# swbox_midi.net
KiCad netlist of a schematic drawn in EAGLE
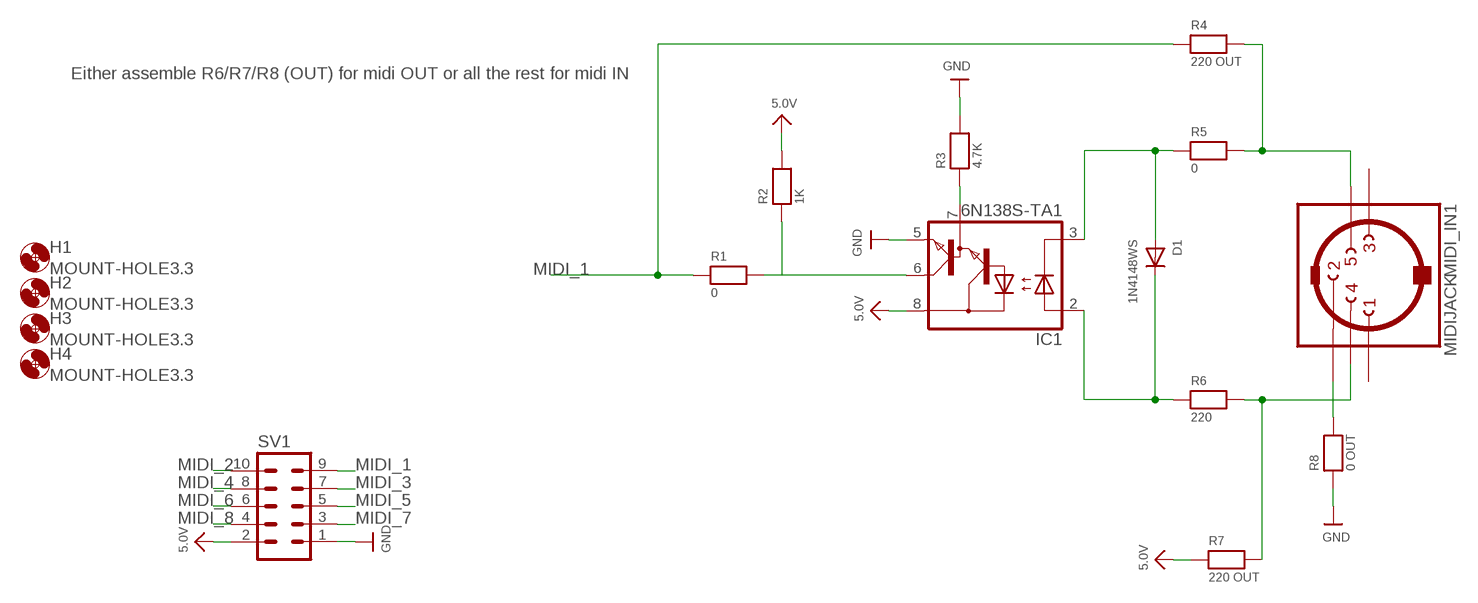
[diagram p0: schematic, sheet 1]
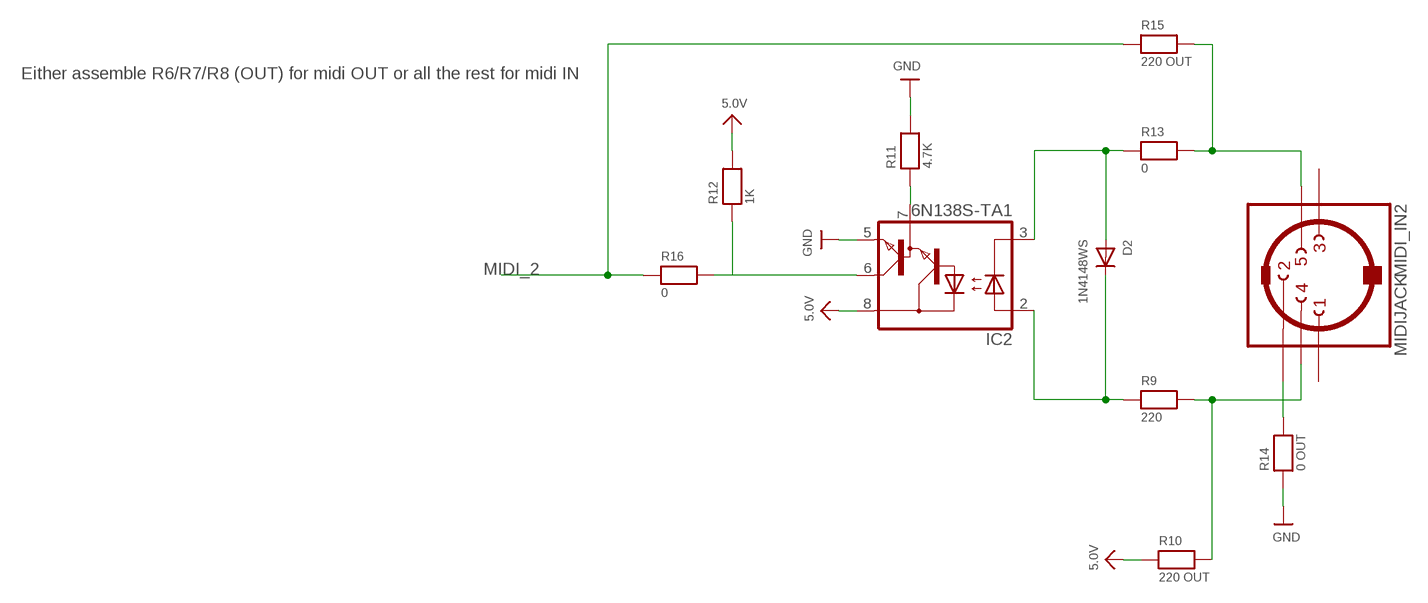
[diagram p1: schematic, sheet 2]
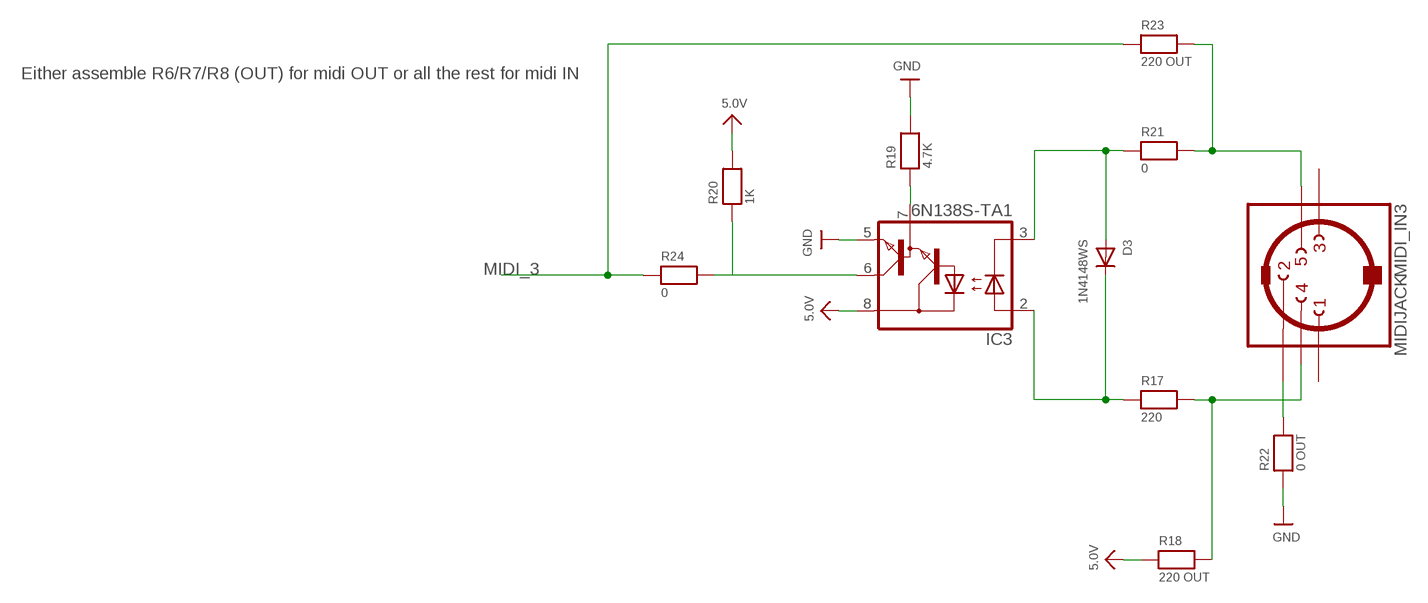
[diagram p2: schematic, sheet 3]
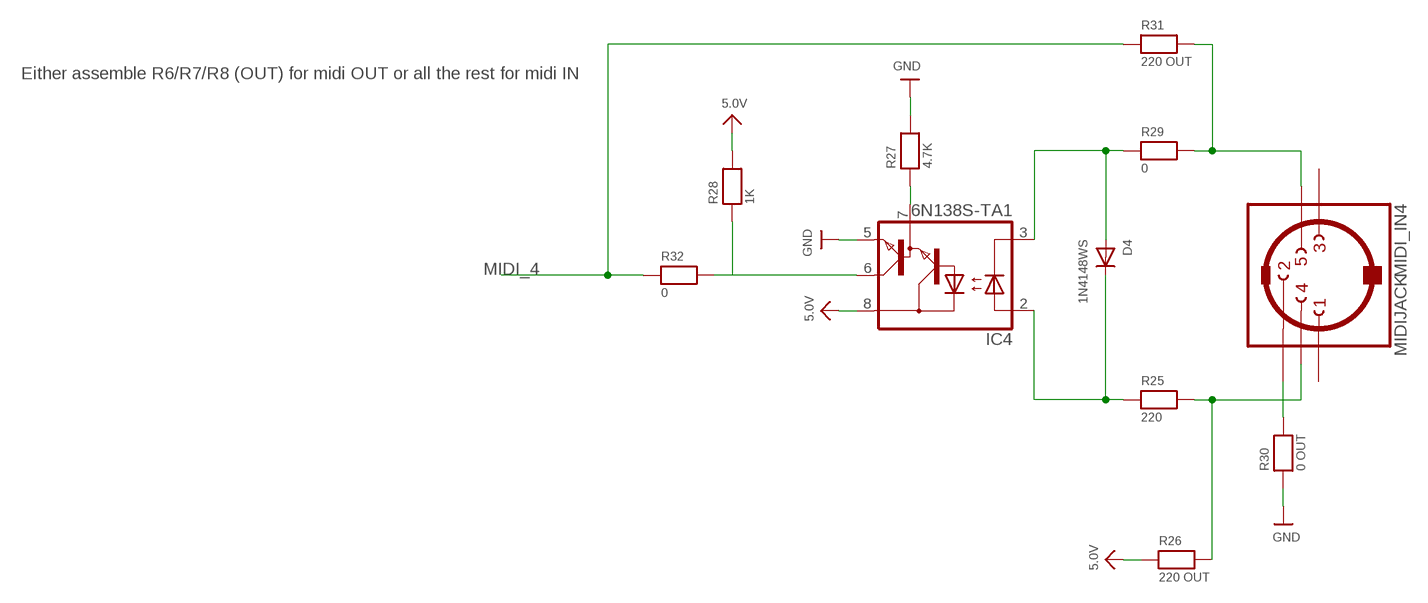
[diagram p3: schematic, sheet 4]
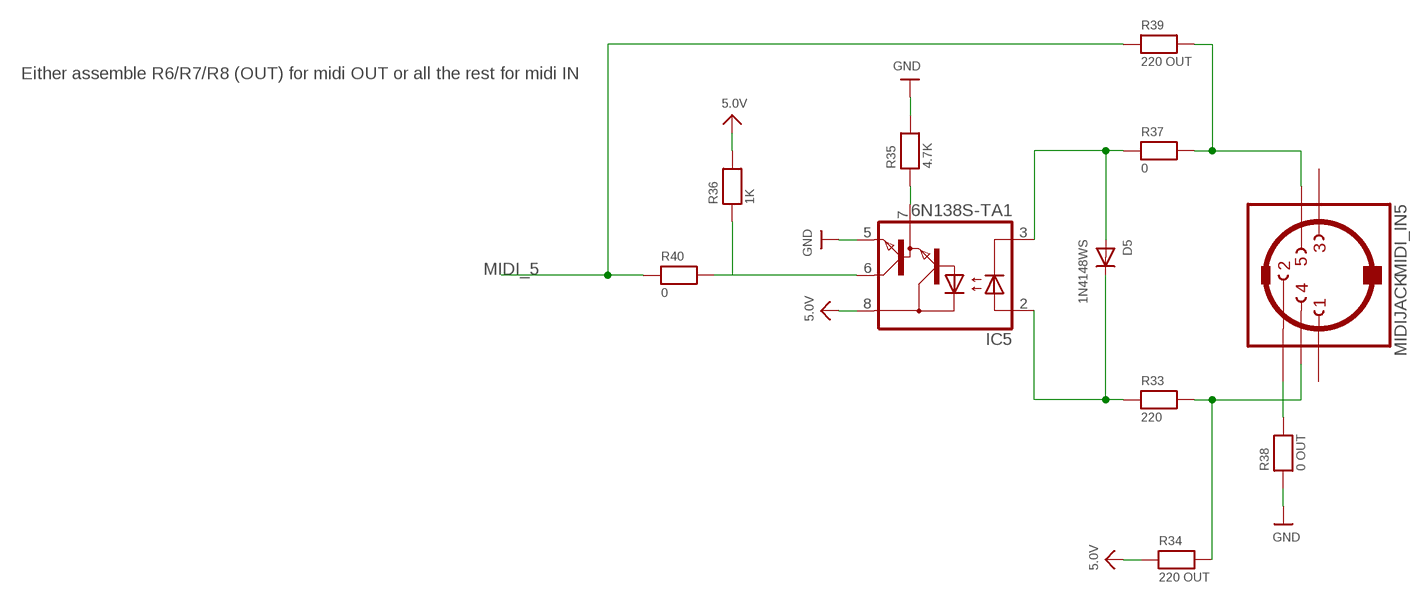
[diagram p4: schematic, sheet 5]
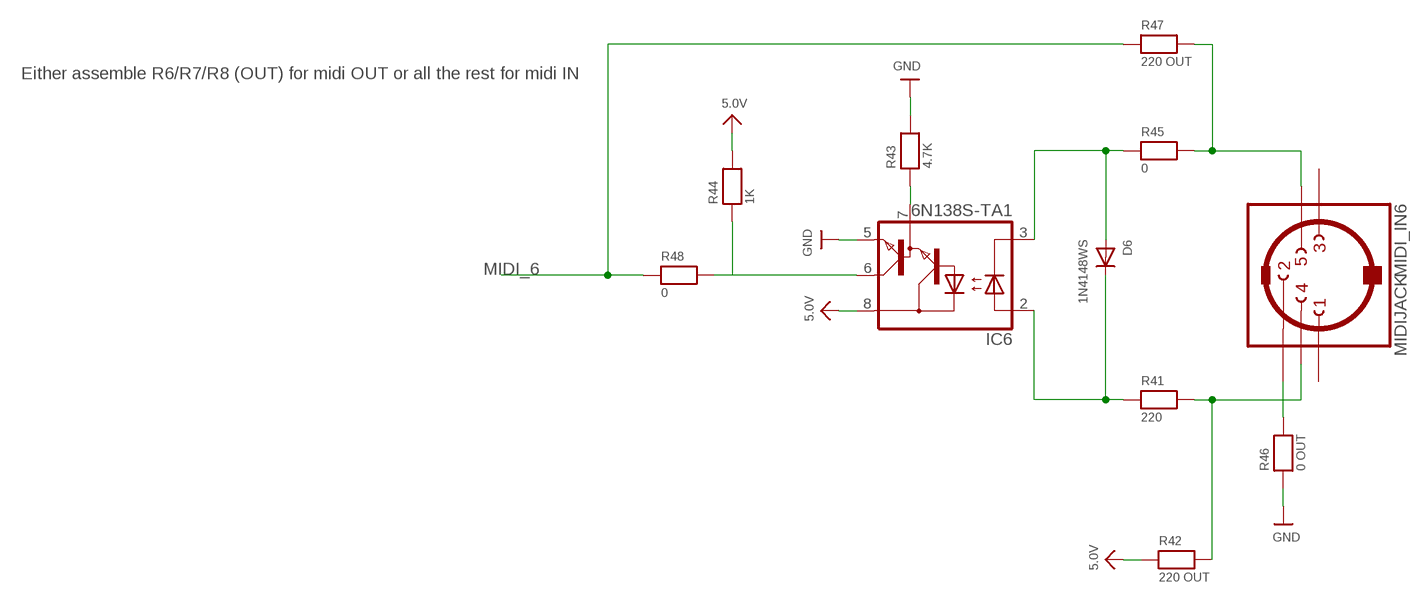
[diagram p5: schematic, sheet 6]
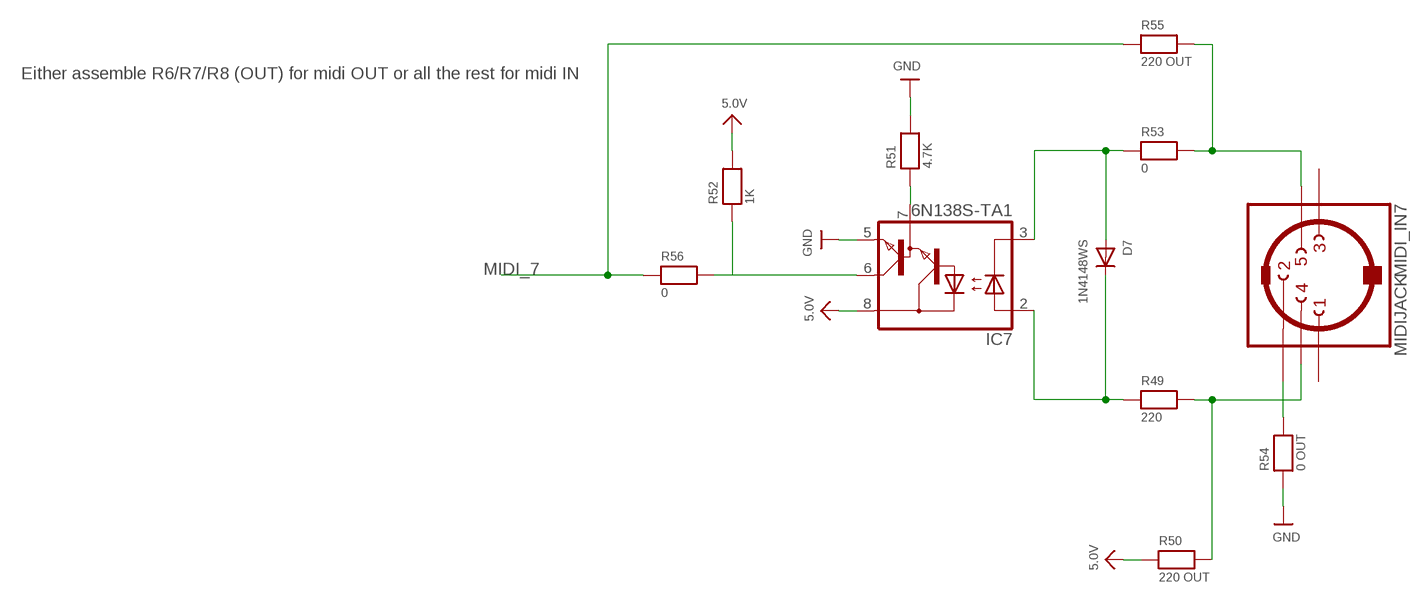
[diagram p6: schematic, sheet 7]
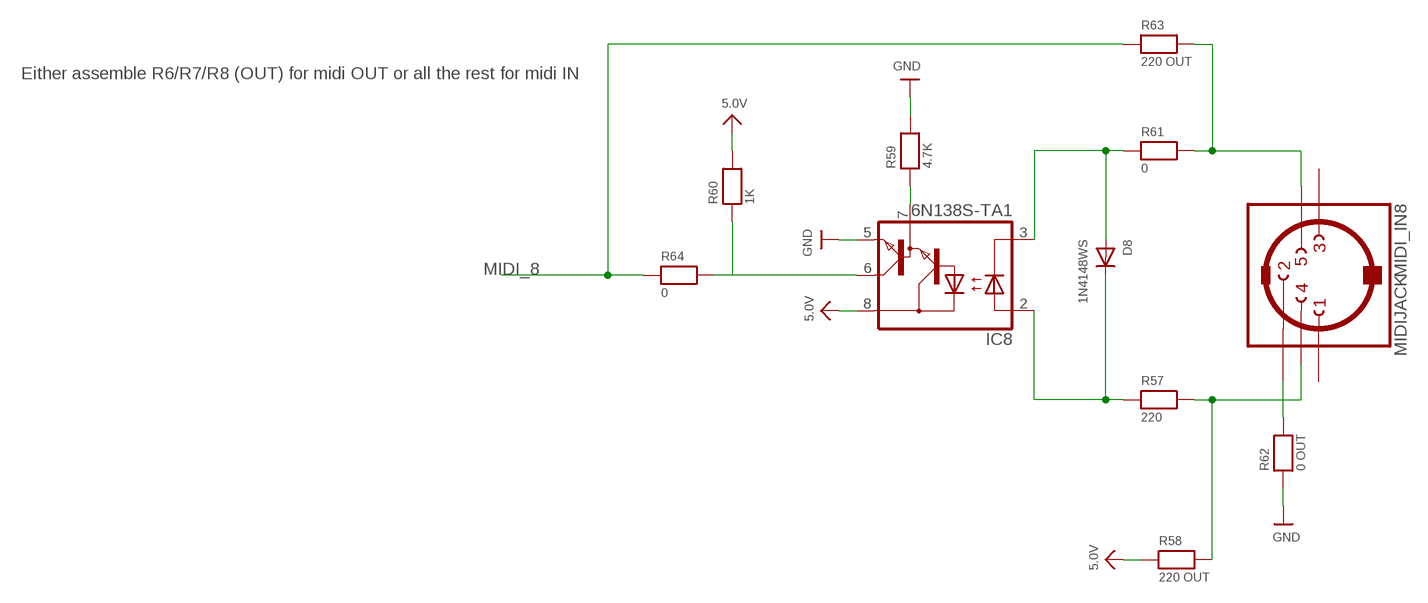
[diagram p7: schematic, sheet 8]

(export (version "E")
  (design (tool "Eeschema 10.0.6"))
  (components
    (comp (ref "D1")
      (value "1N4148WS")
      (footprint "eagle-import:SOD-323")
      (libsource (lib "eagle-import") (part "DIODESOD-323"))
    )
    (comp (ref "H1")
      (value "MOUNT-HOLE3.3")
      (footprint "eagle-import:3,3")
      (libsource (lib "eagle-import") (part "MOUNT-HOLE3.3"))
    )
    (comp (ref "H2")
      (value "MOUNT-HOLE3.3")
      (footprint "eagle-import:3,3")
      (libsource (lib "eagle-import") (part "MOUNT-HOLE3.3"))
    )
    (comp (ref "H3")
      (value "MOUNT-HOLE3.3")
      (footprint "eagle-import:3,3")
      (libsource (lib "eagle-import") (part "MOUNT-HOLE3.3"))
    )
    (comp (ref "H4")
      (value "MOUNT-HOLE3.3")
      (footprint "eagle-import:3,3")
      (libsource (lib "eagle-import") (part "MOUNT-HOLE3.3"))
    )
    (comp (ref "IC1")
      (value "6N138S-TA1")
      (footprint "eagle-import:SO8-GW300")
      (libsource (lib "eagle-import") (part "6N138SMD"))
    )
    (comp (ref "MIDI_IN1")
      (value "MIDIJACK")
      (footprint "eagle-import:CP-2350")
      (libsource (lib "eagle-import") (part "MIDIJACK"))
    )
    (comp (ref "R1")
      (value "0")
      (footprint "eagle-import:_0603")
      (libsource (lib "eagle-import") (part "RESISTOR_0603"))
    )
    (comp (ref "R2")
      (value "1K")
      (footprint "eagle-import:_0603")
      (libsource (lib "eagle-import") (part "RESISTOR_0603"))
    )
    (comp (ref "R3")
      (value "4.7K")
      (footprint "eagle-import:_0603")
      (libsource (lib "eagle-import") (part "RESISTOR_0603"))
    )
    (comp (ref "R4")
      (value "220 OUT")
      (footprint "eagle-import:_0603")
      (libsource (lib "eagle-import") (part "RESISTOR_0603"))
    )
    (comp (ref "R5")
      (value "0")
      (footprint "eagle-import:_0603")
      (libsource (lib "eagle-import") (part "RESISTOR_0603"))
    )
    (comp (ref "R6")
      (value "220")
      (footprint "eagle-import:_0603")
      (libsource (lib "eagle-import") (part "RESISTOR_0603"))
    )
    (comp (ref "R7")
      (value "220 OUT")
      (footprint "eagle-import:_0603")
      (libsource (lib "eagle-import") (part "RESISTOR_0603"))
    )
    (comp (ref "R8")
      (value "0 OUT")
      (footprint "eagle-import:_0603")
      (libsource (lib "eagle-import") (part "RESISTOR_0603"))
    )
    (comp (ref "SV1")
      (value "ML10")
      (footprint "eagle-import:ML10")
      (libsource (lib "eagle-import") (part "ML10"))
    )
    (comp (ref "D5")
      (value "1N4148WS")
      (footprint "eagle-import:SOD-323")
      (libsource (lib "eagle-import") (part "DIODESOD-323"))
    )
    (comp (ref "IC5")
      (value "6N138S-TA1")
      (footprint "eagle-import:SO8-GW300")
      (libsource (lib "eagle-import") (part "6N138SMD"))
    )
    (comp (ref "MIDI_IN5")
      (value "MIDIJACK")
      (footprint "eagle-import:CP-2350")
      (libsource (lib "eagle-import") (part "MIDIJACK"))
    )
    (comp (ref "R33")
      (value "220")
      (footprint "eagle-import:_0603")
      (libsource (lib "eagle-import") (part "RESISTOR_0603"))
    )
    (comp (ref "R34")
      (value "220 OUT")
      (footprint "eagle-import:_0603")
      (libsource (lib "eagle-import") (part "RESISTOR_0603"))
    )
    (comp (ref "R35")
      (value "4.7K")
      (footprint "eagle-import:_0603")
      (libsource (lib "eagle-import") (part "RESISTOR_0603"))
    )
    (comp (ref "R36")
      (value "1K")
      (footprint "eagle-import:_0603")
      (libsource (lib "eagle-import") (part "RESISTOR_0603"))
    )
    (comp (ref "R37")
      (value "0")
      (footprint "eagle-import:_0603")
      (libsource (lib "eagle-import") (part "RESISTOR_0603"))
    )
    (comp (ref "R38")
      (value "0 OUT")
      (footprint "eagle-import:_0603")
      (libsource (lib "eagle-import") (part "RESISTOR_0603"))
    )
    (comp (ref "R39")
      (value "220 OUT")
      (footprint "eagle-import:_0603")
      (libsource (lib "eagle-import") (part "RESISTOR_0603"))
    )
    (comp (ref "R40")
      (value "0")
      (footprint "eagle-import:_0603")
      (libsource (lib "eagle-import") (part "RESISTOR_0603"))
    )
    (comp (ref "D4")
      (value "1N4148WS")
      (footprint "eagle-import:SOD-323")
      (libsource (lib "eagle-import") (part "DIODESOD-323"))
    )
    (comp (ref "IC4")
      (value "6N138S-TA1")
      (footprint "eagle-import:SO8-GW300")
      (libsource (lib "eagle-import") (part "6N138SMD"))
    )
    (comp (ref "MIDI_IN4")
      (value "MIDIJACK")
      (footprint "eagle-import:CP-2350")
      (libsource (lib "eagle-import") (part "MIDIJACK"))
    )
    (comp (ref "R25")
      (value "220")
      (footprint "eagle-import:_0603")
      (libsource (lib "eagle-import") (part "RESISTOR_0603"))
    )
    (comp (ref "R26")
      (value "220 OUT")
      (footprint "eagle-import:_0603")
      (libsource (lib "eagle-import") (part "RESISTOR_0603"))
    )
    (comp (ref "R27")
      (value "4.7K")
      (footprint "eagle-import:_0603")
      (libsource (lib "eagle-import") (part "RESISTOR_0603"))
    )
    (comp (ref "R28")
      (value "1K")
      (footprint "eagle-import:_0603")
      (libsource (lib "eagle-import") (part "RESISTOR_0603"))
    )
    (comp (ref "R29")
      (value "0")
      (footprint "eagle-import:_0603")
      (libsource (lib "eagle-import") (part "RESISTOR_0603"))
    )
    (comp (ref "R30")
      (value "0 OUT")
      (footprint "eagle-import:_0603")
      (libsource (lib "eagle-import") (part "RESISTOR_0603"))
    )
    (comp (ref "R31")
      (value "220 OUT")
      (footprint "eagle-import:_0603")
      (libsource (lib "eagle-import") (part "RESISTOR_0603"))
    )
    (comp (ref "R32")
      (value "0")
      (footprint "eagle-import:_0603")
      (libsource (lib "eagle-import") (part "RESISTOR_0603"))
    )
    (comp (ref "D7")
      (value "1N4148WS")
      (footprint "eagle-import:SOD-323")
      (libsource (lib "eagle-import") (part "DIODESOD-323"))
    )
    (comp (ref "IC7")
      (value "6N138S-TA1")
      (footprint "eagle-import:SO8-GW300")
      (libsource (lib "eagle-import") (part "6N138SMD"))
    )
    (comp (ref "MIDI_IN7")
      (value "MIDIJACK")
      (footprint "eagle-import:CP-2350")
      (libsource (lib "eagle-import") (part "MIDIJACK"))
    )
    (comp (ref "R49")
      (value "220")
      (footprint "eagle-import:_0603")
      (libsource (lib "eagle-import") (part "RESISTOR_0603"))
    )
    (comp (ref "R50")
      (value "220 OUT")
      (footprint "eagle-import:_0603")
      (libsource (lib "eagle-import") (part "RESISTOR_0603"))
    )
    (comp (ref "R51")
      (value "4.7K")
      (footprint "eagle-import:_0603")
      (libsource (lib "eagle-import") (part "RESISTOR_0603"))
    )
    (comp (ref "R52")
      (value "1K")
      (footprint "eagle-import:_0603")
      (libsource (lib "eagle-import") (part "RESISTOR_0603"))
    )
    (comp (ref "R53")
      (value "0")
      (footprint "eagle-import:_0603")
      (libsource (lib "eagle-import") (part "RESISTOR_0603"))
    )
    (comp (ref "R54")
      (value "0 OUT")
      (footprint "eagle-import:_0603")
      (libsource (lib "eagle-import") (part "RESISTOR_0603"))
    )
    (comp (ref "R55")
      (value "220 OUT")
      (footprint "eagle-import:_0603")
      (libsource (lib "eagle-import") (part "RESISTOR_0603"))
    )
    (comp (ref "R56")
      (value "0")
      (footprint "eagle-import:_0603")
      (libsource (lib "eagle-import") (part "RESISTOR_0603"))
    )
    (comp (ref "D6")
      (value "1N4148WS")
      (footprint "eagle-import:SOD-323")
      (libsource (lib "eagle-import") (part "DIODESOD-323"))
    )
    (comp (ref "IC6")
      (value "6N138S-TA1")
      (footprint "eagle-import:SO8-GW300")
      (libsource (lib "eagle-import") (part "6N138SMD"))
    )
    (comp (ref "MIDI_IN6")
      (value "MIDIJACK")
      (footprint "eagle-import:CP-2350")
      (libsource (lib "eagle-import") (part "MIDIJACK"))
    )
    (comp (ref "R41")
      (value "220")
      (footprint "eagle-import:_0603")
      (libsource (lib "eagle-import") (part "RESISTOR_0603"))
    )
    (comp (ref "R42")
      (value "220 OUT")
      (footprint "eagle-import:_0603")
      (libsource (lib "eagle-import") (part "RESISTOR_0603"))
    )
    (comp (ref "R43")
      (value "4.7K")
      (footprint "eagle-import:_0603")
      (libsource (lib "eagle-import") (part "RESISTOR_0603"))
    )
    (comp (ref "R44")
      (value "1K")
      (footprint "eagle-import:_0603")
      (libsource (lib "eagle-import") (part "RESISTOR_0603"))
    )
    (comp (ref "R45")
      (value "0")
      (footprint "eagle-import:_0603")
      (libsource (lib "eagle-import") (part "RESISTOR_0603"))
    )
    (comp (ref "R46")
      (value "0 OUT")
      (footprint "eagle-import:_0603")
      (libsource (lib "eagle-import") (part "RESISTOR_0603"))
    )
    (comp (ref "R47")
      (value "220 OUT")
      (footprint "eagle-import:_0603")
      (libsource (lib "eagle-import") (part "RESISTOR_0603"))
    )
    (comp (ref "R48")
      (value "0")
      (footprint "eagle-import:_0603")
      (libsource (lib "eagle-import") (part "RESISTOR_0603"))
    )
    (comp (ref "D2")
      (value "1N4148WS")
      (footprint "eagle-import:SOD-323")
      (libsource (lib "eagle-import") (part "DIODESOD-323"))
    )
    (comp (ref "IC2")
      (value "6N138S-TA1")
      (footprint "eagle-import:SO8-GW300")
      (libsource (lib "eagle-import") (part "6N138SMD"))
    )
    (comp (ref "MIDI_IN2")
      (value "MIDIJACK")
      (footprint "eagle-import:CP-2350")
      (libsource (lib "eagle-import") (part "MIDIJACK"))
    )
    (comp (ref "R9")
      (value "220")
      (footprint "eagle-import:_0603")
      (libsource (lib "eagle-import") (part "RESISTOR_0603"))
    )
    (comp (ref "R10")
      (value "220 OUT")
      (footprint "eagle-import:_0603")
      (libsource (lib "eagle-import") (part "RESISTOR_0603"))
    )
    (comp (ref "R11")
      (value "4.7K")
      (footprint "eagle-import:_0603")
      (libsource (lib "eagle-import") (part "RESISTOR_0603"))
    )
    (comp (ref "R12")
      (value "1K")
      (footprint "eagle-import:_0603")
      (libsource (lib "eagle-import") (part "RESISTOR_0603"))
    )
    (comp (ref "R13")
      (value "0")
      (footprint "eagle-import:_0603")
      (libsource (lib "eagle-import") (part "RESISTOR_0603"))
    )
    (comp (ref "R14")
      (value "0 OUT")
      (footprint "eagle-import:_0603")
      (libsource (lib "eagle-import") (part "RESISTOR_0603"))
    )
    (comp (ref "R15")
      (value "220 OUT")
      (footprint "eagle-import:_0603")
      (libsource (lib "eagle-import") (part "RESISTOR_0603"))
    )
    (comp (ref "R16")
      (value "0")
      (footprint "eagle-import:_0603")
      (libsource (lib "eagle-import") (part "RESISTOR_0603"))
    )
    (comp (ref "D3")
      (value "1N4148WS")
      (footprint "eagle-import:SOD-323")
      (libsource (lib "eagle-import") (part "DIODESOD-323"))
    )
    (comp (ref "IC3")
      (value "6N138S-TA1")
      (footprint "eagle-import:SO8-GW300")
      (libsource (lib "eagle-import") (part "6N138SMD"))
    )
    (comp (ref "MIDI_IN3")
      (value "MIDIJACK")
      (footprint "eagle-import:CP-2350")
      (libsource (lib "eagle-import") (part "MIDIJACK"))
    )
    (comp (ref "R17")
      (value "220")
      (footprint "eagle-import:_0603")
      (libsource (lib "eagle-import") (part "RESISTOR_0603"))
    )
    (comp (ref "R18")
      (value "220 OUT")
      (footprint "eagle-import:_0603")
      (libsource (lib "eagle-import") (part "RESISTOR_0603"))
    )
    (comp (ref "R19")
      (value "4.7K")
      (footprint "eagle-import:_0603")
      (libsource (lib "eagle-import") (part "RESISTOR_0603"))
    )
    (comp (ref "R20")
      (value "1K")
      (footprint "eagle-import:_0603")
      (libsource (lib "eagle-import") (part "RESISTOR_0603"))
    )
    (comp (ref "R21")
      (value "0")
      (footprint "eagle-import:_0603")
      (libsource (lib "eagle-import") (part "RESISTOR_0603"))
    )
    (comp (ref "R22")
      (value "0 OUT")
      (footprint "eagle-import:_0603")
      (libsource (lib "eagle-import") (part "RESISTOR_0603"))
    )
    (comp (ref "R23")
      (value "220 OUT")
      (footprint "eagle-import:_0603")
      (libsource (lib "eagle-import") (part "RESISTOR_0603"))
    )
    (comp (ref "R24")
      (value "0")
      (footprint "eagle-import:_0603")
      (libsource (lib "eagle-import") (part "RESISTOR_0603"))
    )
    (comp (ref "D8")
      (value "1N4148WS")
      (footprint "eagle-import:SOD-323")
      (libsource (lib "eagle-import") (part "DIODESOD-323"))
    )
    (comp (ref "IC8")
      (value "6N138S-TA1")
      (footprint "eagle-import:SO8-GW300")
      (libsource (lib "eagle-import") (part "6N138SMD"))
    )
    (comp (ref "MIDI_IN8")
      (value "MIDIJACK")
      (footprint "eagle-import:CP-2350")
      (libsource (lib "eagle-import") (part "MIDIJACK"))
    )
    (comp (ref "R57")
      (value "220")
      (footprint "eagle-import:_0603")
      (libsource (lib "eagle-import") (part "RESISTOR_0603"))
    )
    (comp (ref "R58")
      (value "220 OUT")
      (footprint "eagle-import:_0603")
      (libsource (lib "eagle-import") (part "RESISTOR_0603"))
    )
    (comp (ref "R59")
      (value "4.7K")
      (footprint "eagle-import:_0603")
      (libsource (lib "eagle-import") (part "RESISTOR_0603"))
    )
    (comp (ref "R60")
      (value "1K")
      (footprint "eagle-import:_0603")
      (libsource (lib "eagle-import") (part "RESISTOR_0603"))
    )
    (comp (ref "R61")
      (value "0")
      (footprint "eagle-import:_0603")
      (libsource (lib "eagle-import") (part "RESISTOR_0603"))
    )
    (comp (ref "R62")
      (value "0 OUT")
      (footprint "eagle-import:_0603")
      (libsource (lib "eagle-import") (part "RESISTOR_0603"))
    )
    (comp (ref "R63")
      (value "220 OUT")
      (footprint "eagle-import:_0603")
      (libsource (lib "eagle-import") (part "RESISTOR_0603"))
    )
    (comp (ref "R64")
      (value "0")
      (footprint "eagle-import:_0603")
      (libsource (lib "eagle-import") (part "RESISTOR_0603"))
    )
  )
  (nets
    (net (code "1") (name "5.0V") (class "Default")
      (node (ref "IC1") (pin "8") (pinfunction "VCC_8") (pintype "passive"))
      (node (ref "IC2") (pin "8") (pinfunction "VCC_8") (pintype "passive"))
      (node (ref "IC3") (pin "8") (pinfunction "VCC_8") (pintype "passive"))
      (node (ref "IC4") (pin "8") (pinfunction "VCC_8") (pintype "passive"))
      (node (ref "IC5") (pin "8") (pinfunction "VCC_8") (pintype "passive"))
      (node (ref "IC6") (pin "8") (pinfunction "VCC_8") (pintype "passive"))
      (node (ref "IC7") (pin "8") (pinfunction "VCC_8") (pintype "passive"))
      (node (ref "IC8") (pin "8") (pinfunction "VCC_8") (pintype "passive"))
      (node (ref "R10") (pin "1") (pinfunction "1_1") (pintype "passive"))
      (node (ref "R12") (pin "2") (pinfunction "2_2") (pintype "passive"))
      (node (ref "R18") (pin "1") (pinfunction "1_1") (pintype "passive"))
      (node (ref "R2") (pin "2") (pinfunction "2_2") (pintype "passive"))
      (node (ref "R20") (pin "2") (pinfunction "2_2") (pintype "passive"))
      (node (ref "R26") (pin "1") (pinfunction "1_1") (pintype "passive"))
      (node (ref "R28") (pin "2") (pinfunction "2_2") (pintype "passive"))
      (node (ref "R34") (pin "1") (pinfunction "1_1") (pintype "passive"))
      (node (ref "R36") (pin "2") (pinfunction "2_2") (pintype "passive"))
      (node (ref "R42") (pin "1") (pinfunction "1_1") (pintype "passive"))
      (node (ref "R44") (pin "2") (pinfunction "2_2") (pintype "passive"))
      (node (ref "R50") (pin "1") (pinfunction "1_1") (pintype "passive"))
      (node (ref "R52") (pin "2") (pinfunction "2_2") (pintype "passive"))
      (node (ref "R58") (pin "1") (pinfunction "1_1") (pintype "passive"))
      (node (ref "R60") (pin "2") (pinfunction "2_2") (pintype "passive"))
      (node (ref "R7") (pin "1") (pinfunction "1_1") (pintype "passive"))
      (node (ref "SV1") (pin "2") (pinfunction "2_2") (pintype "passive"))
    )
    (net (code "2") (name "GND") (class "Default")
      (node (ref "IC1") (pin "5") (pinfunction "GND_5") (pintype "passive"))
      (node (ref "IC2") (pin "5") (pinfunction "GND_5") (pintype "passive"))
      (node (ref "IC3") (pin "5") (pinfunction "GND_5") (pintype "passive"))
      (node (ref "IC4") (pin "5") (pinfunction "GND_5") (pintype "passive"))
      (node (ref "IC5") (pin "5") (pinfunction "GND_5") (pintype "passive"))
      (node (ref "IC6") (pin "5") (pinfunction "GND_5") (pintype "passive"))
      (node (ref "IC7") (pin "5") (pinfunction "GND_5") (pintype "passive"))
      (node (ref "IC8") (pin "5") (pinfunction "GND_5") (pintype "passive"))
      (node (ref "R11") (pin "2") (pinfunction "2_2") (pintype "passive"))
      (node (ref "R14") (pin "1") (pinfunction "1_1") (pintype "passive"))
      (node (ref "R19") (pin "2") (pinfunction "2_2") (pintype "passive"))
      (node (ref "R22") (pin "1") (pinfunction "1_1") (pintype "passive"))
      (node (ref "R27") (pin "2") (pinfunction "2_2") (pintype "passive"))
      (node (ref "R3") (pin "2") (pinfunction "2_2") (pintype "passive"))
      (node (ref "R30") (pin "1") (pinfunction "1_1") (pintype "passive"))
      (node (ref "R35") (pin "2") (pinfunction "2_2") (pintype "passive"))
      (node (ref "R38") (pin "1") (pinfunction "1_1") (pintype "passive"))
      (node (ref "R43") (pin "2") (pinfunction "2_2") (pintype "passive"))
      (node (ref "R46") (pin "1") (pinfunction "1_1") (pintype "passive"))
      (node (ref "R51") (pin "2") (pinfunction "2_2") (pintype "passive"))
      (node (ref "R54") (pin "1") (pinfunction "1_1") (pintype "passive"))
      (node (ref "R59") (pin "2") (pinfunction "2_2") (pintype "passive"))
      (node (ref "R62") (pin "1") (pinfunction "1_1") (pintype "passive"))
      (node (ref "R8") (pin "1") (pinfunction "1_1") (pintype "passive"))
      (node (ref "SV1") (pin "1") (pinfunction "1_1") (pintype "passive"))
    )
    (net (code "3") (name "MIDI_1") (class "Default")
      (node (ref "R1") (pin "1") (pinfunction "1_1") (pintype "passive"))
      (node (ref "R4") (pin "1") (pinfunction "1_1") (pintype "passive"))
      (node (ref "SV1") (pin "9") (pinfunction "9_9") (pintype "passive"))
    )
    (net (code "4") (name "MIDI_2") (class "Default")
      (node (ref "R15") (pin "1") (pinfunction "1_1") (pintype "passive"))
      (node (ref "R16") (pin "1") (pinfunction "1_1") (pintype "passive"))
      (node (ref "SV1") (pin "10") (pinfunction "10_10") (pintype "passive"))
    )
    (net (code "5") (name "MIDI_3") (class "Default")
      (node (ref "R23") (pin "1") (pinfunction "1_1") (pintype "passive"))
      (node (ref "R24") (pin "1") (pinfunction "1_1") (pintype "passive"))
      (node (ref "SV1") (pin "7") (pinfunction "7_7") (pintype "passive"))
    )
    (net (code "6") (name "MIDI_4") (class "Default")
      (node (ref "R31") (pin "1") (pinfunction "1_1") (pintype "passive"))
      (node (ref "R32") (pin "1") (pinfunction "1_1") (pintype "passive"))
      (node (ref "SV1") (pin "8") (pinfunction "8_8") (pintype "passive"))
    )
    (net (code "7") (name "MIDI_5") (class "Default")
      (node (ref "R39") (pin "1") (pinfunction "1_1") (pintype "passive"))
      (node (ref "R40") (pin "1") (pinfunction "1_1") (pintype "passive"))
      (node (ref "SV1") (pin "5") (pinfunction "5_5") (pintype "passive"))
    )
    (net (code "8") (name "MIDI_6") (class "Default")
      (node (ref "R47") (pin "1") (pinfunction "1_1") (pintype "passive"))
      (node (ref "R48") (pin "1") (pinfunction "1_1") (pintype "passive"))
      (node (ref "SV1") (pin "6") (pinfunction "6_6") (pintype "passive"))
    )
    (net (code "9") (name "MIDI_7") (class "Default")
      (node (ref "R55") (pin "1") (pinfunction "1_1") (pintype "passive"))
      (node (ref "R56") (pin "1") (pinfunction "1_1") (pintype "passive"))
      (node (ref "SV1") (pin "3") (pinfunction "3_3") (pintype "passive"))
    )
    (net (code "10") (name "MIDI_8") (class "Default")
      (node (ref "R63") (pin "1") (pinfunction "1_1") (pintype "passive"))
      (node (ref "R64") (pin "1") (pinfunction "1_1") (pintype "passive"))
      (node (ref "SV1") (pin "4") (pinfunction "4_4") (pintype "passive"))
    )
    (net (code "11") (name "Net-(IC1-A)") (class "Default")
      (node (ref "D1") (pin "C") (pinfunction "C_C") (pintype "passive"))
      (node (ref "IC1") (pin "2") (pinfunction "A_2") (pintype "passive"))
      (node (ref "R6") (pin "1") (pinfunction "1_1") (pintype "passive"))
    )
    (net (code "12") (name "Net-(IC1-C)") (class "Default")
      (node (ref "D1") (pin "A") (pinfunction "A_A") (pintype "passive"))
      (node (ref "IC1") (pin "3") (pinfunction "C_3") (pintype "passive"))
      (node (ref "R5") (pin "1") (pinfunction "1_1") (pintype "passive"))
    )
    (net (code "13") (name "Net-(IC1-VB)") (class "Default")
      (node (ref "IC1") (pin "7") (pinfunction "VB_7") (pintype "passive"))
      (node (ref "R3") (pin "1") (pinfunction "1_1") (pintype "passive"))
    )
    (net (code "14") (name "Net-(IC1-VO)") (class "Default")
      (node (ref "IC1") (pin "6") (pinfunction "VO_6") (pintype "passive"))
      (node (ref "R1") (pin "2") (pinfunction "2_2") (pintype "passive"))
      (node (ref "R2") (pin "1") (pinfunction "1_1") (pintype "passive"))
    )
    (net (code "15") (name "Net-(IC2-A)") (class "Default")
      (node (ref "D2") (pin "C") (pinfunction "C_C") (pintype "passive"))
      (node (ref "IC2") (pin "2") (pinfunction "A_2") (pintype "passive"))
      (node (ref "R9") (pin "1") (pinfunction "1_1") (pintype "passive"))
    )
    (net (code "16") (name "Net-(IC2-C)") (class "Default")
      (node (ref "D2") (pin "A") (pinfunction "A_A") (pintype "passive"))
      (node (ref "IC2") (pin "3") (pinfunction "C_3") (pintype "passive"))
      (node (ref "R13") (pin "1") (pinfunction "1_1") (pintype "passive"))
    )
    (net (code "17") (name "Net-(IC2-VB)") (class "Default")
      (node (ref "IC2") (pin "7") (pinfunction "VB_7") (pintype "passive"))
      (node (ref "R11") (pin "1") (pinfunction "1_1") (pintype "passive"))
    )
    (net (code "18") (name "Net-(IC2-VO)") (class "Default")
      (node (ref "IC2") (pin "6") (pinfunction "VO_6") (pintype "passive"))
      (node (ref "R12") (pin "1") (pinfunction "1_1") (pintype "passive"))
      (node (ref "R16") (pin "2") (pinfunction "2_2") (pintype "passive"))
    )
    (net (code "19") (name "Net-(IC3-A)") (class "Default")
      (node (ref "D3") (pin "C") (pinfunction "C_C") (pintype "passive"))
      (node (ref "IC3") (pin "2") (pinfunction "A_2") (pintype "passive"))
      (node (ref "R17") (pin "1") (pinfunction "1_1") (pintype "passive"))
    )
    (net (code "20") (name "Net-(IC3-C)") (class "Default")
      (node (ref "D3") (pin "A") (pinfunction "A_A") (pintype "passive"))
      (node (ref "IC3") (pin "3") (pinfunction "C_3") (pintype "passive"))
      (node (ref "R21") (pin "1") (pinfunction "1_1") (pintype "passive"))
    )
    (net (code "21") (name "Net-(IC3-VB)") (class "Default")
      (node (ref "IC3") (pin "7") (pinfunction "VB_7") (pintype "passive"))
      (node (ref "R19") (pin "1") (pinfunction "1_1") (pintype "passive"))
    )
    (net (code "22") (name "Net-(IC3-VO)") (class "Default")
      (node (ref "IC3") (pin "6") (pinfunction "VO_6") (pintype "passive"))
      (node (ref "R20") (pin "1") (pinfunction "1_1") (pintype "passive"))
      (node (ref "R24") (pin "2") (pinfunction "2_2") (pintype "passive"))
    )
    (net (code "23") (name "Net-(IC4-A)") (class "Default")
      (node (ref "D4") (pin "C") (pinfunction "C_C") (pintype "passive"))
      (node (ref "IC4") (pin "2") (pinfunction "A_2") (pintype "passive"))
      (node (ref "R25") (pin "1") (pinfunction "1_1") (pintype "passive"))
    )
    (net (code "24") (name "Net-(IC4-C)") (class "Default")
      (node (ref "D4") (pin "A") (pinfunction "A_A") (pintype "passive"))
      (node (ref "IC4") (pin "3") (pinfunction "C_3") (pintype "passive"))
      (node (ref "R29") (pin "1") (pinfunction "1_1") (pintype "passive"))
    )
    (net (code "25") (name "Net-(IC4-VB)") (class "Default")
      (node (ref "IC4") (pin "7") (pinfunction "VB_7") (pintype "passive"))
      (node (ref "R27") (pin "1") (pinfunction "1_1") (pintype "passive"))
    )
    (net (code "26") (name "Net-(IC4-VO)") (class "Default")
      (node (ref "IC4") (pin "6") (pinfunction "VO_6") (pintype "passive"))
      (node (ref "R28") (pin "1") (pinfunction "1_1") (pintype "passive"))
      (node (ref "R32") (pin "2") (pinfunction "2_2") (pintype "passive"))
    )
    (net (code "27") (name "Net-(IC5-A)") (class "Default")
      (node (ref "D5") (pin "C") (pinfunction "C_C") (pintype "passive"))
      (node (ref "IC5") (pin "2") (pinfunction "A_2") (pintype "passive"))
      (node (ref "R33") (pin "1") (pinfunction "1_1") (pintype "passive"))
    )
    (net (code "28") (name "Net-(IC5-C)") (class "Default")
      (node (ref "D5") (pin "A") (pinfunction "A_A") (pintype "passive"))
      (node (ref "IC5") (pin "3") (pinfunction "C_3") (pintype "passive"))
      (node (ref "R37") (pin "1") (pinfunction "1_1") (pintype "passive"))
    )
    (net (code "29") (name "Net-(IC5-VB)") (class "Default")
      (node (ref "IC5") (pin "7") (pinfunction "VB_7") (pintype "passive"))
      (node (ref "R35") (pin "1") (pinfunction "1_1") (pintype "passive"))
    )
    (net (code "30") (name "Net-(IC5-VO)") (class "Default")
      (node (ref "IC5") (pin "6") (pinfunction "VO_6") (pintype "passive"))
      (node (ref "R36") (pin "1") (pinfunction "1_1") (pintype "passive"))
      (node (ref "R40") (pin "2") (pinfunction "2_2") (pintype "passive"))
    )
    (net (code "31") (name "Net-(IC6-A)") (class "Default")
      (node (ref "D6") (pin "C") (pinfunction "C_C") (pintype "passive"))
      (node (ref "IC6") (pin "2") (pinfunction "A_2") (pintype "passive"))
      (node (ref "R41") (pin "1") (pinfunction "1_1") (pintype "passive"))
    )
    (net (code "32") (name "Net-(IC6-C)") (class "Default")
      (node (ref "D6") (pin "A") (pinfunction "A_A") (pintype "passive"))
      (node (ref "IC6") (pin "3") (pinfunction "C_3") (pintype "passive"))
      (node (ref "R45") (pin "1") (pinfunction "1_1") (pintype "passive"))
    )
    (net (code "33") (name "Net-(IC6-VB)") (class "Default")
      (node (ref "IC6") (pin "7") (pinfunction "VB_7") (pintype "passive"))
      (node (ref "R43") (pin "1") (pinfunction "1_1") (pintype "passive"))
    )
    (net (code "34") (name "Net-(IC6-VO)") (class "Default")
      (node (ref "IC6") (pin "6") (pinfunction "VO_6") (pintype "passive"))
      (node (ref "R44") (pin "1") (pinfunction "1_1") (pintype "passive"))
      (node (ref "R48") (pin "2") (pinfunction "2_2") (pintype "passive"))
    )
    (net (code "35") (name "Net-(IC7-A)") (class "Default")
      (node (ref "D7") (pin "C") (pinfunction "C_C") (pintype "passive"))
      (node (ref "IC7") (pin "2") (pinfunction "A_2") (pintype "passive"))
      (node (ref "R49") (pin "1") (pinfunction "1_1") (pintype "passive"))
    )
    (net (code "36") (name "Net-(IC7-C)") (class "Default")
      (node (ref "D7") (pin "A") (pinfunction "A_A") (pintype "passive"))
      (node (ref "IC7") (pin "3") (pinfunction "C_3") (pintype "passive"))
      (node (ref "R53") (pin "1") (pinfunction "1_1") (pintype "passive"))
    )
    (net (code "37") (name "Net-(IC7-VB)") (class "Default")
      (node (ref "IC7") (pin "7") (pinfunction "VB_7") (pintype "passive"))
      (node (ref "R51") (pin "1") (pinfunction "1_1") (pintype "passive"))
    )
    (net (code "38") (name "Net-(IC7-VO)") (class "Default")
      (node (ref "IC7") (pin "6") (pinfunction "VO_6") (pintype "passive"))
      (node (ref "R52") (pin "1") (pinfunction "1_1") (pintype "passive"))
      (node (ref "R56") (pin "2") (pinfunction "2_2") (pintype "passive"))
    )
    (net (code "39") (name "Net-(IC8-A)") (class "Default")
      (node (ref "D8") (pin "C") (pinfunction "C_C") (pintype "passive"))
      (node (ref "IC8") (pin "2") (pinfunction "A_2") (pintype "passive"))
      (node (ref "R57") (pin "1") (pinfunction "1_1") (pintype "passive"))
    )
    (net (code "40") (name "Net-(IC8-C)") (class "Default")
      (node (ref "D8") (pin "A") (pinfunction "A_A") (pintype "passive"))
      (node (ref "IC8") (pin "3") (pinfunction "C_3") (pintype "passive"))
      (node (ref "R61") (pin "1") (pinfunction "1_1") (pintype "passive"))
    )
    (net (code "41") (name "Net-(IC8-VB)") (class "Default")
      (node (ref "IC8") (pin "7") (pinfunction "VB_7") (pintype "passive"))
      (node (ref "R59") (pin "1") (pinfunction "1_1") (pintype "passive"))
    )
    (net (code "42") (name "Net-(IC8-VO)") (class "Default")
      (node (ref "IC8") (pin "6") (pinfunction "VO_6") (pintype "passive"))
      (node (ref "R60") (pin "1") (pinfunction "1_1") (pintype "passive"))
      (node (ref "R64") (pin "2") (pinfunction "2_2") (pintype "passive"))
    )
    (net (code "43") (name "Net-(MIDI_IN1-Pad2)") (class "Default")
      (node (ref "MIDI_IN1") (pin "2") (pinfunction "2_2") (pintype "passive"))
      (node (ref "R8") (pin "2") (pinfunction "2_2") (pintype "passive"))
    )
    (net (code "44") (name "Net-(MIDI_IN1-Pad4)") (class "Default")
      (node (ref "MIDI_IN1") (pin "4") (pinfunction "4_4") (pintype "passive"))
      (node (ref "R6") (pin "2") (pinfunction "2_2") (pintype "passive"))
      (node (ref "R7") (pin "2") (pinfunction "2_2") (pintype "passive"))
    )
    (net (code "45") (name "Net-(MIDI_IN1-Pad5)") (class "Default")
      (node (ref "MIDI_IN1") (pin "5") (pinfunction "5_5") (pintype "passive"))
      (node (ref "R4") (pin "2") (pinfunction "2_2") (pintype "passive"))
      (node (ref "R5") (pin "2") (pinfunction "2_2") (pintype "passive"))
    )
    (net (code "46") (name "Net-(MIDI_IN2-Pad2)") (class "Default")
      (node (ref "MIDI_IN2") (pin "2") (pinfunction "2_2") (pintype "passive"))
      (node (ref "R14") (pin "2") (pinfunction "2_2") (pintype "passive"))
    )
    (net (code "47") (name "Net-(MIDI_IN2-Pad4)") (class "Default")
      (node (ref "MIDI_IN2") (pin "4") (pinfunction "4_4") (pintype "passive"))
      (node (ref "R10") (pin "2") (pinfunction "2_2") (pintype "passive"))
      (node (ref "R9") (pin "2") (pinfunction "2_2") (pintype "passive"))
    )
    (net (code "48") (name "Net-(MIDI_IN2-Pad5)") (class "Default")
      (node (ref "MIDI_IN2") (pin "5") (pinfunction "5_5") (pintype "passive"))
      (node (ref "R13") (pin "2") (pinfunction "2_2") (pintype "passive"))
      (node (ref "R15") (pin "2") (pinfunction "2_2") (pintype "passive"))
    )
    (net (code "49") (name "Net-(MIDI_IN3-Pad2)") (class "Default")
      (node (ref "MIDI_IN3") (pin "2") (pinfunction "2_2") (pintype "passive"))
      (node (ref "R22") (pin "2") (pinfunction "2_2") (pintype "passive"))
    )
    (net (code "50") (name "Net-(MIDI_IN3-Pad4)") (class "Default")
      (node (ref "MIDI_IN3") (pin "4") (pinfunction "4_4") (pintype "passive"))
      (node (ref "R17") (pin "2") (pinfunction "2_2") (pintype "passive"))
      (node (ref "R18") (pin "2") (pinfunction "2_2") (pintype "passive"))
    )
    (net (code "51") (name "Net-(MIDI_IN3-Pad5)") (class "Default")
      (node (ref "MIDI_IN3") (pin "5") (pinfunction "5_5") (pintype "passive"))
      (node (ref "R21") (pin "2") (pinfunction "2_2") (pintype "passive"))
      (node (ref "R23") (pin "2") (pinfunction "2_2") (pintype "passive"))
    )
    (net (code "52") (name "Net-(MIDI_IN4-Pad2)") (class "Default")
      (node (ref "MIDI_IN4") (pin "2") (pinfunction "2_2") (pintype "passive"))
      (node (ref "R30") (pin "2") (pinfunction "2_2") (pintype "passive"))
    )
    (net (code "53") (name "Net-(MIDI_IN4-Pad4)") (class "Default")
      (node (ref "MIDI_IN4") (pin "4") (pinfunction "4_4") (pintype "passive"))
      (node (ref "R25") (pin "2") (pinfunction "2_2") (pintype "passive"))
      (node (ref "R26") (pin "2") (pinfunction "2_2") (pintype "passive"))
    )
    (net (code "54") (name "Net-(MIDI_IN4-Pad5)") (class "Default")
      (node (ref "MIDI_IN4") (pin "5") (pinfunction "5_5") (pintype "passive"))
      (node (ref "R29") (pin "2") (pinfunction "2_2") (pintype "passive"))
      (node (ref "R31") (pin "2") (pinfunction "2_2") (pintype "passive"))
    )
    (net (code "55") (name "Net-(MIDI_IN5-Pad2)") (class "Default")
      (node (ref "MIDI_IN5") (pin "2") (pinfunction "2_2") (pintype "passive"))
      (node (ref "R38") (pin "2") (pinfunction "2_2") (pintype "passive"))
    )
    (net (code "56") (name "Net-(MIDI_IN5-Pad4)") (class "Default")
      (node (ref "MIDI_IN5") (pin "4") (pinfunction "4_4") (pintype "passive"))
      (node (ref "R33") (pin "2") (pinfunction "2_2") (pintype "passive"))
      (node (ref "R34") (pin "2") (pinfunction "2_2") (pintype "passive"))
    )
    (net (code "57") (name "Net-(MIDI_IN5-Pad5)") (class "Default")
      (node (ref "MIDI_IN5") (pin "5") (pinfunction "5_5") (pintype "passive"))
      (node (ref "R37") (pin "2") (pinfunction "2_2") (pintype "passive"))
      (node (ref "R39") (pin "2") (pinfunction "2_2") (pintype "passive"))
    )
    (net (code "58") (name "Net-(MIDI_IN6-Pad2)") (class "Default")
      (node (ref "MIDI_IN6") (pin "2") (pinfunction "2_2") (pintype "passive"))
      (node (ref "R46") (pin "2") (pinfunction "2_2") (pintype "passive"))
    )
    (net (code "59") (name "Net-(MIDI_IN6-Pad4)") (class "Default")
      (node (ref "MIDI_IN6") (pin "4") (pinfunction "4_4") (pintype "passive"))
      (node (ref "R41") (pin "2") (pinfunction "2_2") (pintype "passive"))
      (node (ref "R42") (pin "2") (pinfunction "2_2") (pintype "passive"))
    )
    (net (code "60") (name "Net-(MIDI_IN6-Pad5)") (class "Default")
      (node (ref "MIDI_IN6") (pin "5") (pinfunction "5_5") (pintype "passive"))
      (node (ref "R45") (pin "2") (pinfunction "2_2") (pintype "passive"))
      (node (ref "R47") (pin "2") (pinfunction "2_2") (pintype "passive"))
    )
    (net (code "61") (name "Net-(MIDI_IN7-Pad2)") (class "Default")
      (node (ref "MIDI_IN7") (pin "2") (pinfunction "2_2") (pintype "passive"))
      (node (ref "R54") (pin "2") (pinfunction "2_2") (pintype "passive"))
    )
    (net (code "62") (name "Net-(MIDI_IN7-Pad4)") (class "Default")
      (node (ref "MIDI_IN7") (pin "4") (pinfunction "4_4") (pintype "passive"))
      (node (ref "R49") (pin "2") (pinfunction "2_2") (pintype "passive"))
      (node (ref "R50") (pin "2") (pinfunction "2_2") (pintype "passive"))
    )
    (net (code "63") (name "Net-(MIDI_IN7-Pad5)") (class "Default")
      (node (ref "MIDI_IN7") (pin "5") (pinfunction "5_5") (pintype "passive"))
      (node (ref "R53") (pin "2") (pinfunction "2_2") (pintype "passive"))
      (node (ref "R55") (pin "2") (pinfunction "2_2") (pintype "passive"))
    )
    (net (code "64") (name "Net-(MIDI_IN8-Pad2)") (class "Default")
      (node (ref "MIDI_IN8") (pin "2") (pinfunction "2_2") (pintype "passive"))
      (node (ref "R62") (pin "2") (pinfunction "2_2") (pintype "passive"))
    )
    (net (code "65") (name "Net-(MIDI_IN8-Pad4)") (class "Default")
      (node (ref "MIDI_IN8") (pin "4") (pinfunction "4_4") (pintype "passive"))
      (node (ref "R57") (pin "2") (pinfunction "2_2") (pintype "passive"))
      (node (ref "R58") (pin "2") (pinfunction "2_2") (pintype "passive"))
    )
    (net (code "66") (name "Net-(MIDI_IN8-Pad5)") (class "Default")
      (node (ref "MIDI_IN8") (pin "5") (pinfunction "5_5") (pintype "passive"))
      (node (ref "R61") (pin "2") (pinfunction "2_2") (pintype "passive"))
      (node (ref "R63") (pin "2") (pinfunction "2_2") (pintype "passive"))
    )
    (net (code "67") (name "unconnected-(MIDI_IN1-Pad1)") (class "Default")
      (node (ref "MIDI_IN1") (pin "1") (pinfunction "1_1") (pintype "passive"))
    )
    (net (code "68") (name "unconnected-(MIDI_IN1-Pad3)") (class "Default")
      (node (ref "MIDI_IN1") (pin "3") (pinfunction "3_3") (pintype "passive"))
    )
    (net (code "69") (name "unconnected-(MIDI_IN2-Pad1)") (class "Default")
      (node (ref "MIDI_IN2") (pin "1") (pinfunction "1_1") (pintype "passive"))
    )
    (net (code "70") (name "unconnected-(MIDI_IN2-Pad3)") (class "Default")
      (node (ref "MIDI_IN2") (pin "3") (pinfunction "3_3") (pintype "passive"))
    )
    (net (code "71") (name "unconnected-(MIDI_IN3-Pad1)") (class "Default")
      (node (ref "MIDI_IN3") (pin "1") (pinfunction "1_1") (pintype "passive"))
    )
    (net (code "72") (name "unconnected-(MIDI_IN3-Pad3)") (class "Default")
      (node (ref "MIDI_IN3") (pin "3") (pinfunction "3_3") (pintype "passive"))
    )
    (net (code "73") (name "unconnected-(MIDI_IN4-Pad1)") (class "Default")
      (node (ref "MIDI_IN4") (pin "1") (pinfunction "1_1") (pintype "passive"))
    )
    (net (code "74") (name "unconnected-(MIDI_IN4-Pad3)") (class "Default")
      (node (ref "MIDI_IN4") (pin "3") (pinfunction "3_3") (pintype "passive"))
    )
    (net (code "75") (name "unconnected-(MIDI_IN5-Pad1)") (class "Default")
      (node (ref "MIDI_IN5") (pin "1") (pinfunction "1_1") (pintype "passive"))
    )
    (net (code "76") (name "unconnected-(MIDI_IN5-Pad3)") (class "Default")
      (node (ref "MIDI_IN5") (pin "3") (pinfunction "3_3") (pintype "passive"))
    )
    (net (code "77") (name "unconnected-(MIDI_IN6-Pad1)") (class "Default")
      (node (ref "MIDI_IN6") (pin "1") (pinfunction "1_1") (pintype "passive"))
    )
    (net (code "78") (name "unconnected-(MIDI_IN6-Pad3)") (class "Default")
      (node (ref "MIDI_IN6") (pin "3") (pinfunction "3_3") (pintype "passive"))
    )
    (net (code "79") (name "unconnected-(MIDI_IN7-Pad1)") (class "Default")
      (node (ref "MIDI_IN7") (pin "1") (pinfunction "1_1") (pintype "passive"))
    )
    (net (code "80") (name "unconnected-(MIDI_IN7-Pad3)") (class "Default")
      (node (ref "MIDI_IN7") (pin "3") (pinfunction "3_3") (pintype "passive"))
    )
    (net (code "81") (name "unconnected-(MIDI_IN8-Pad1)") (class "Default")
      (node (ref "MIDI_IN8") (pin "1") (pinfunction "1_1") (pintype "passive"))
    )
    (net (code "82") (name "unconnected-(MIDI_IN8-Pad3)") (class "Default")
      (node (ref "MIDI_IN8") (pin "3") (pinfunction "3_3") (pintype "passive"))
    )
  )
)
